# stm32-usb-ble-devkit.net
KiCad netlist of a schematic drawn in EAGLE
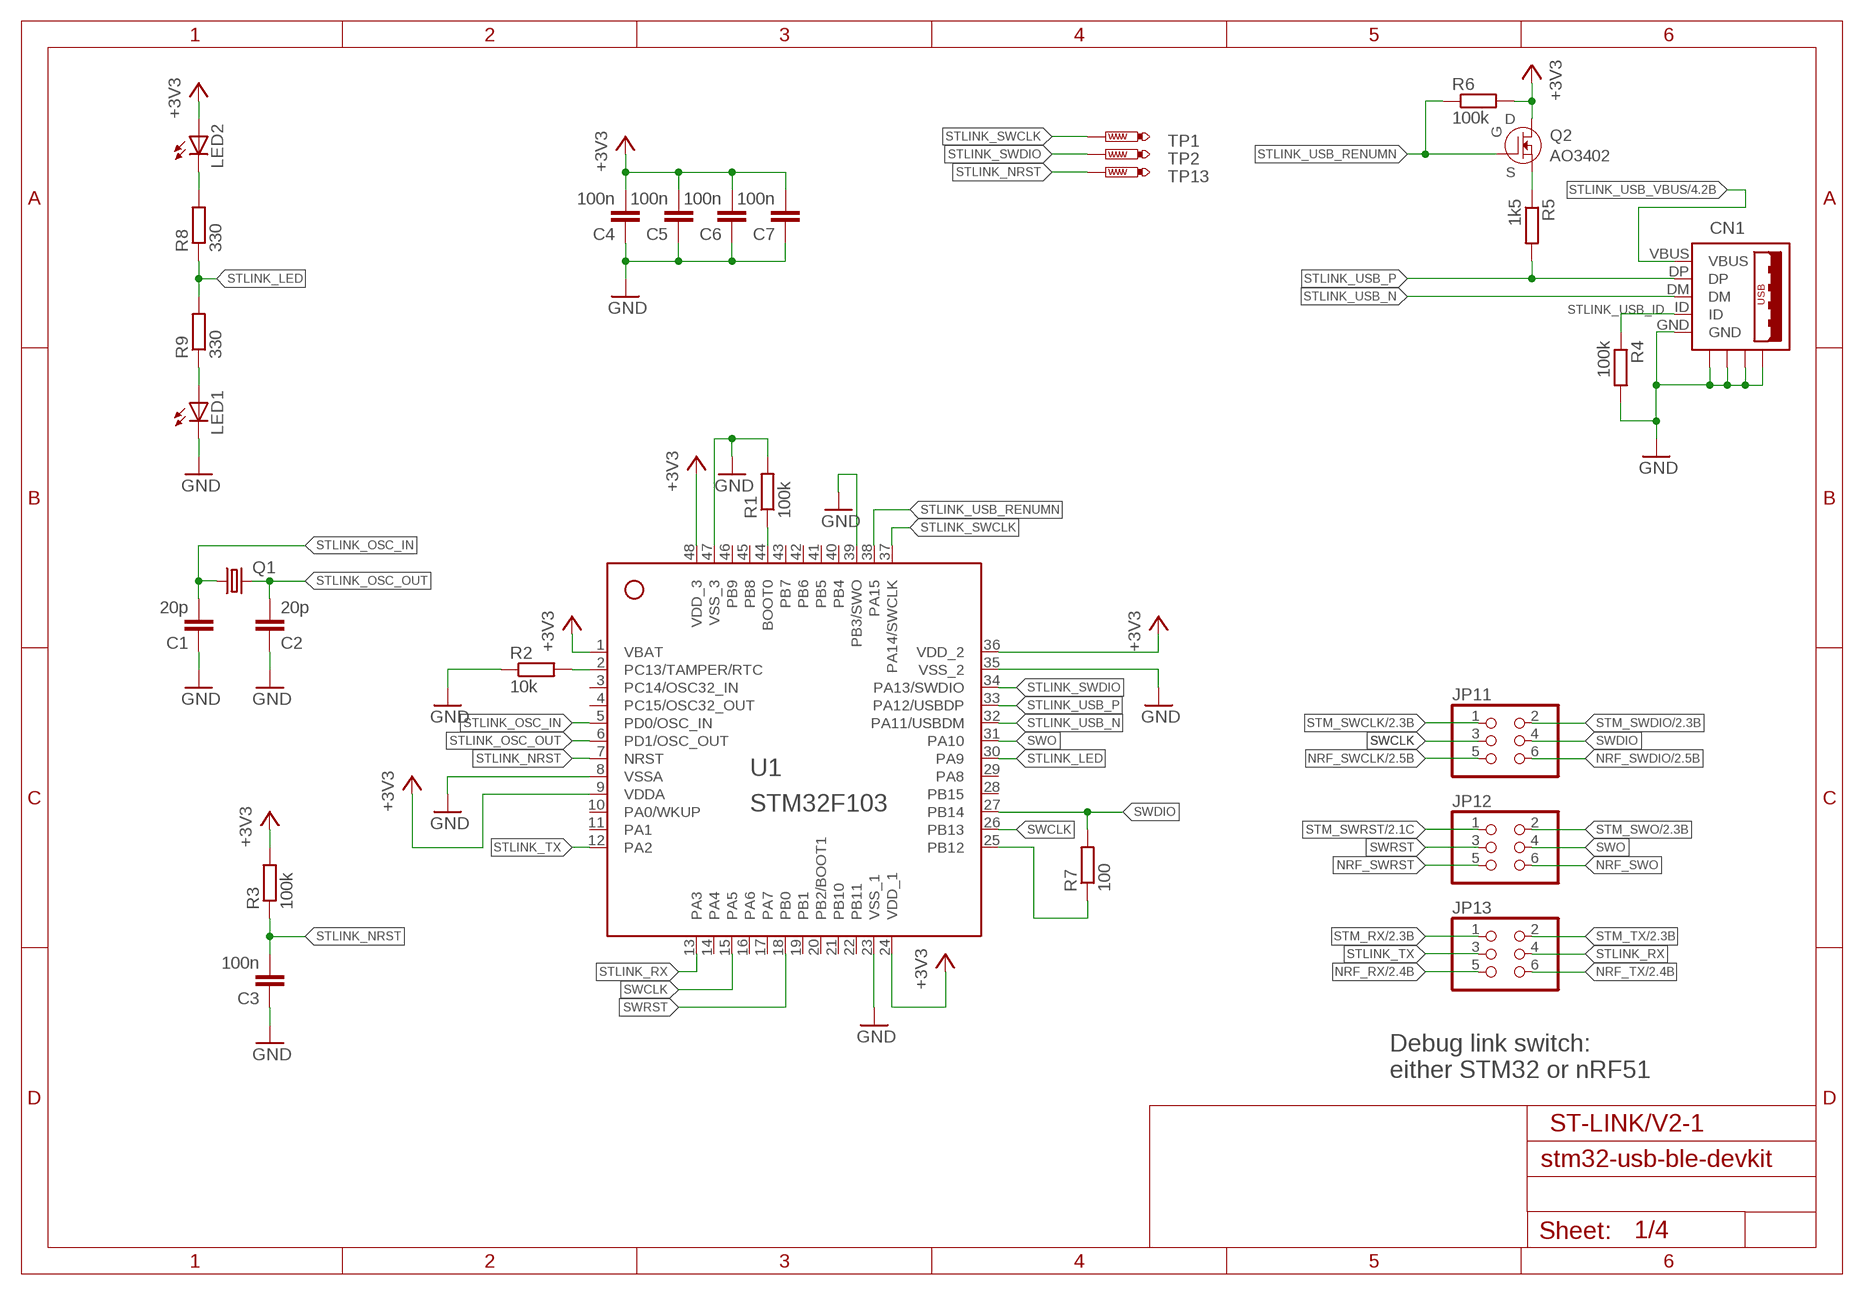
[diagram p0: schematic, sheet 1]
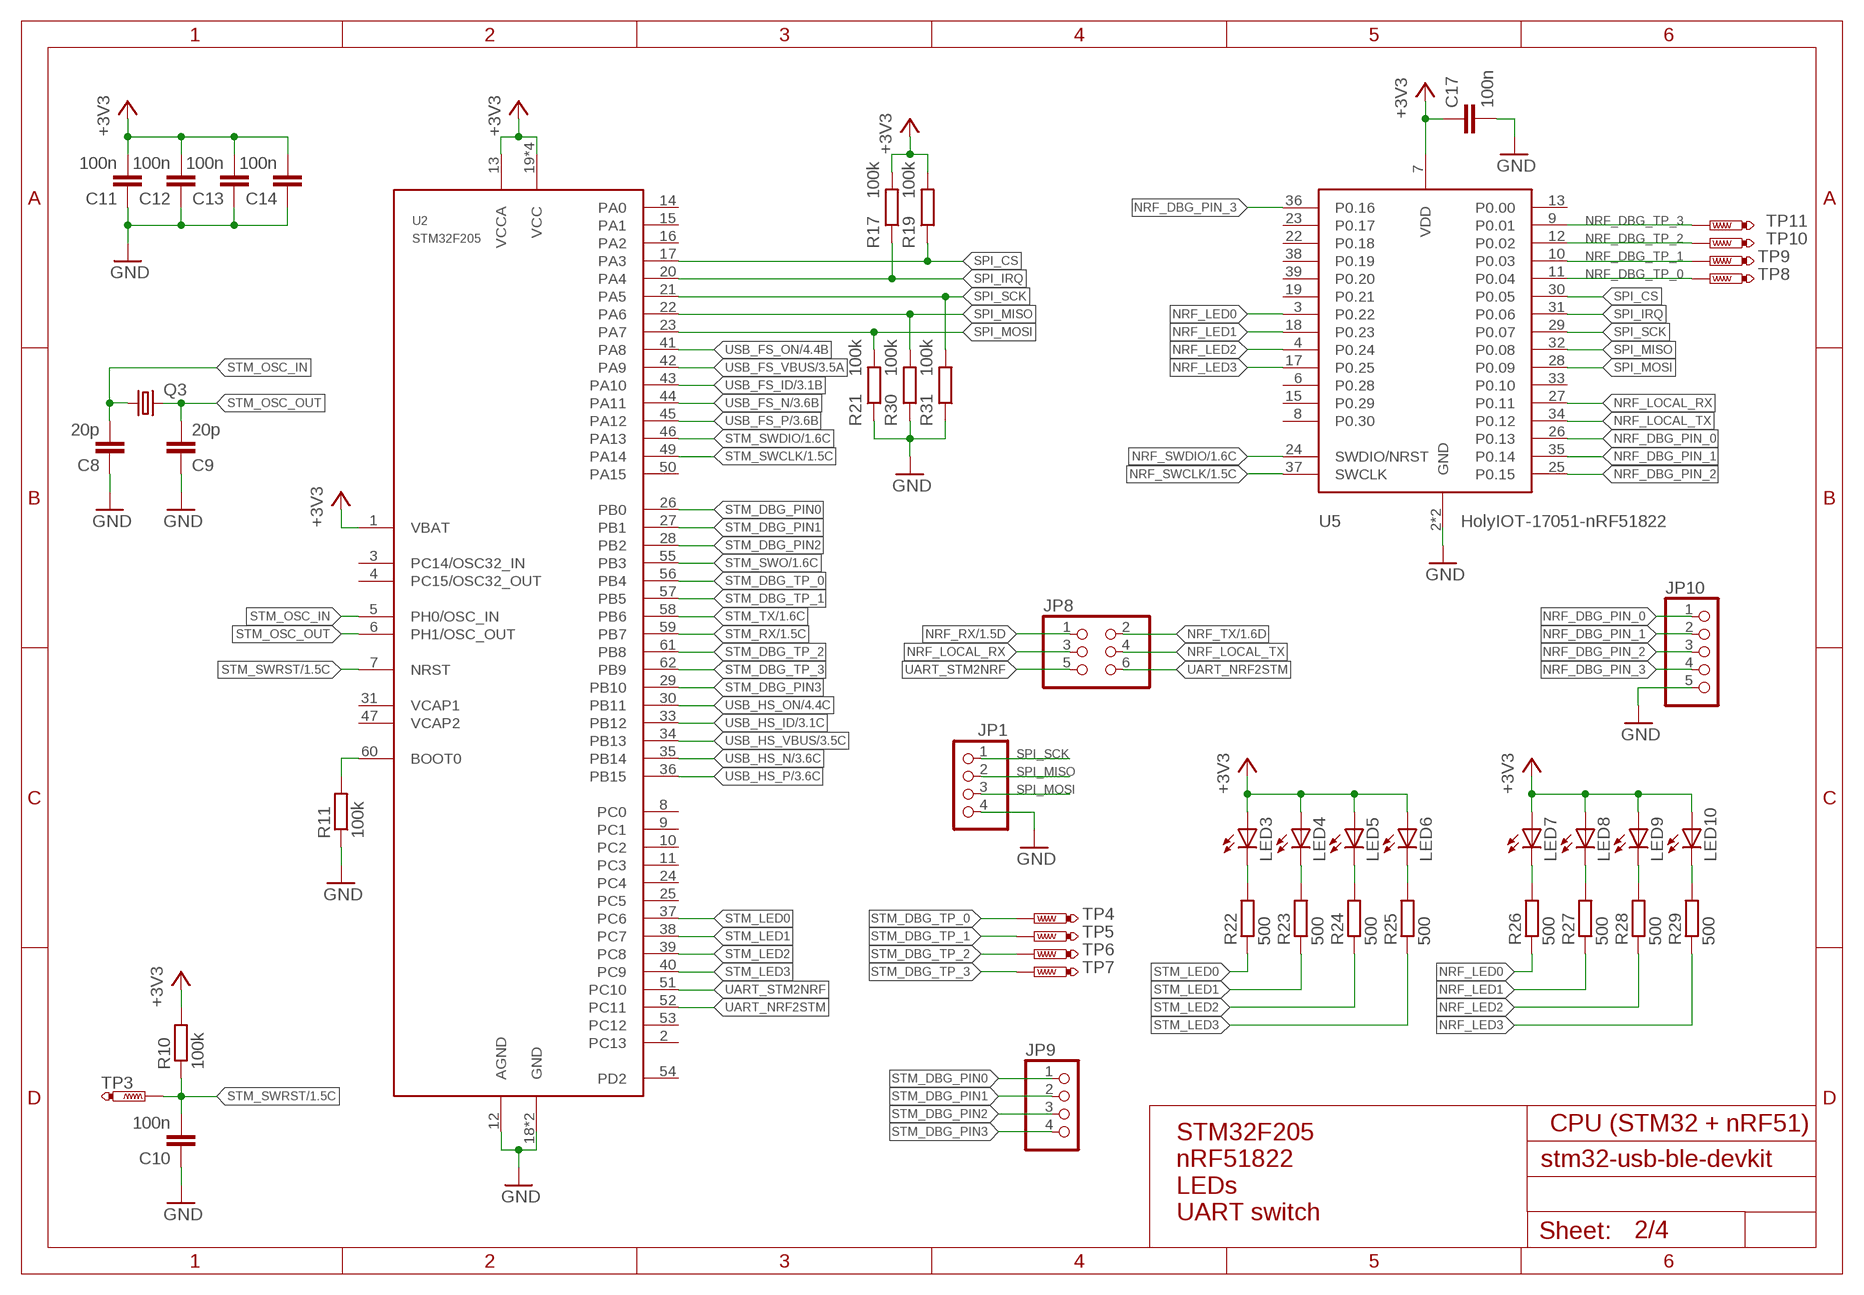
[diagram p1: schematic, sheet 2]
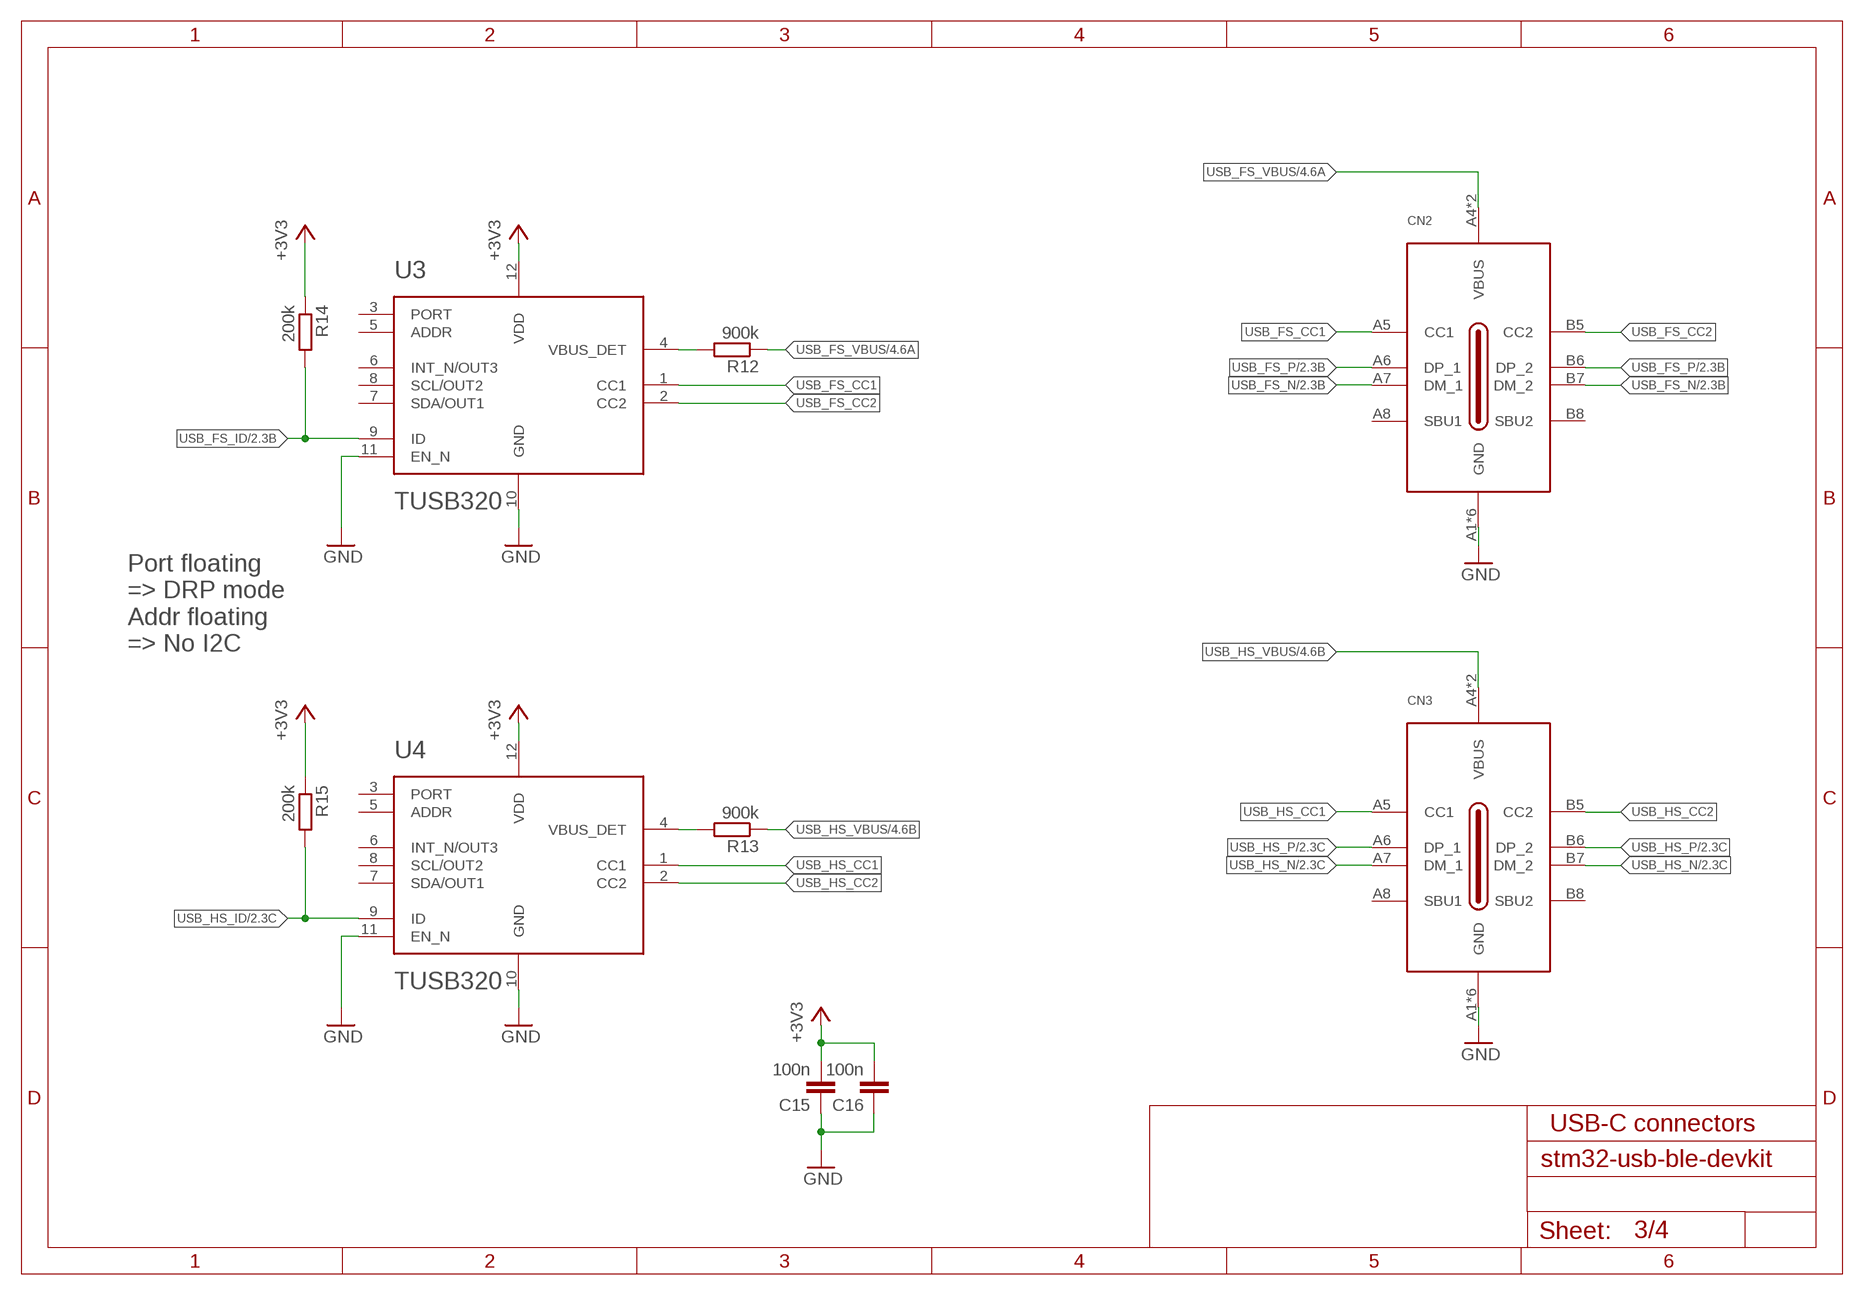
[diagram p2: schematic, sheet 3]
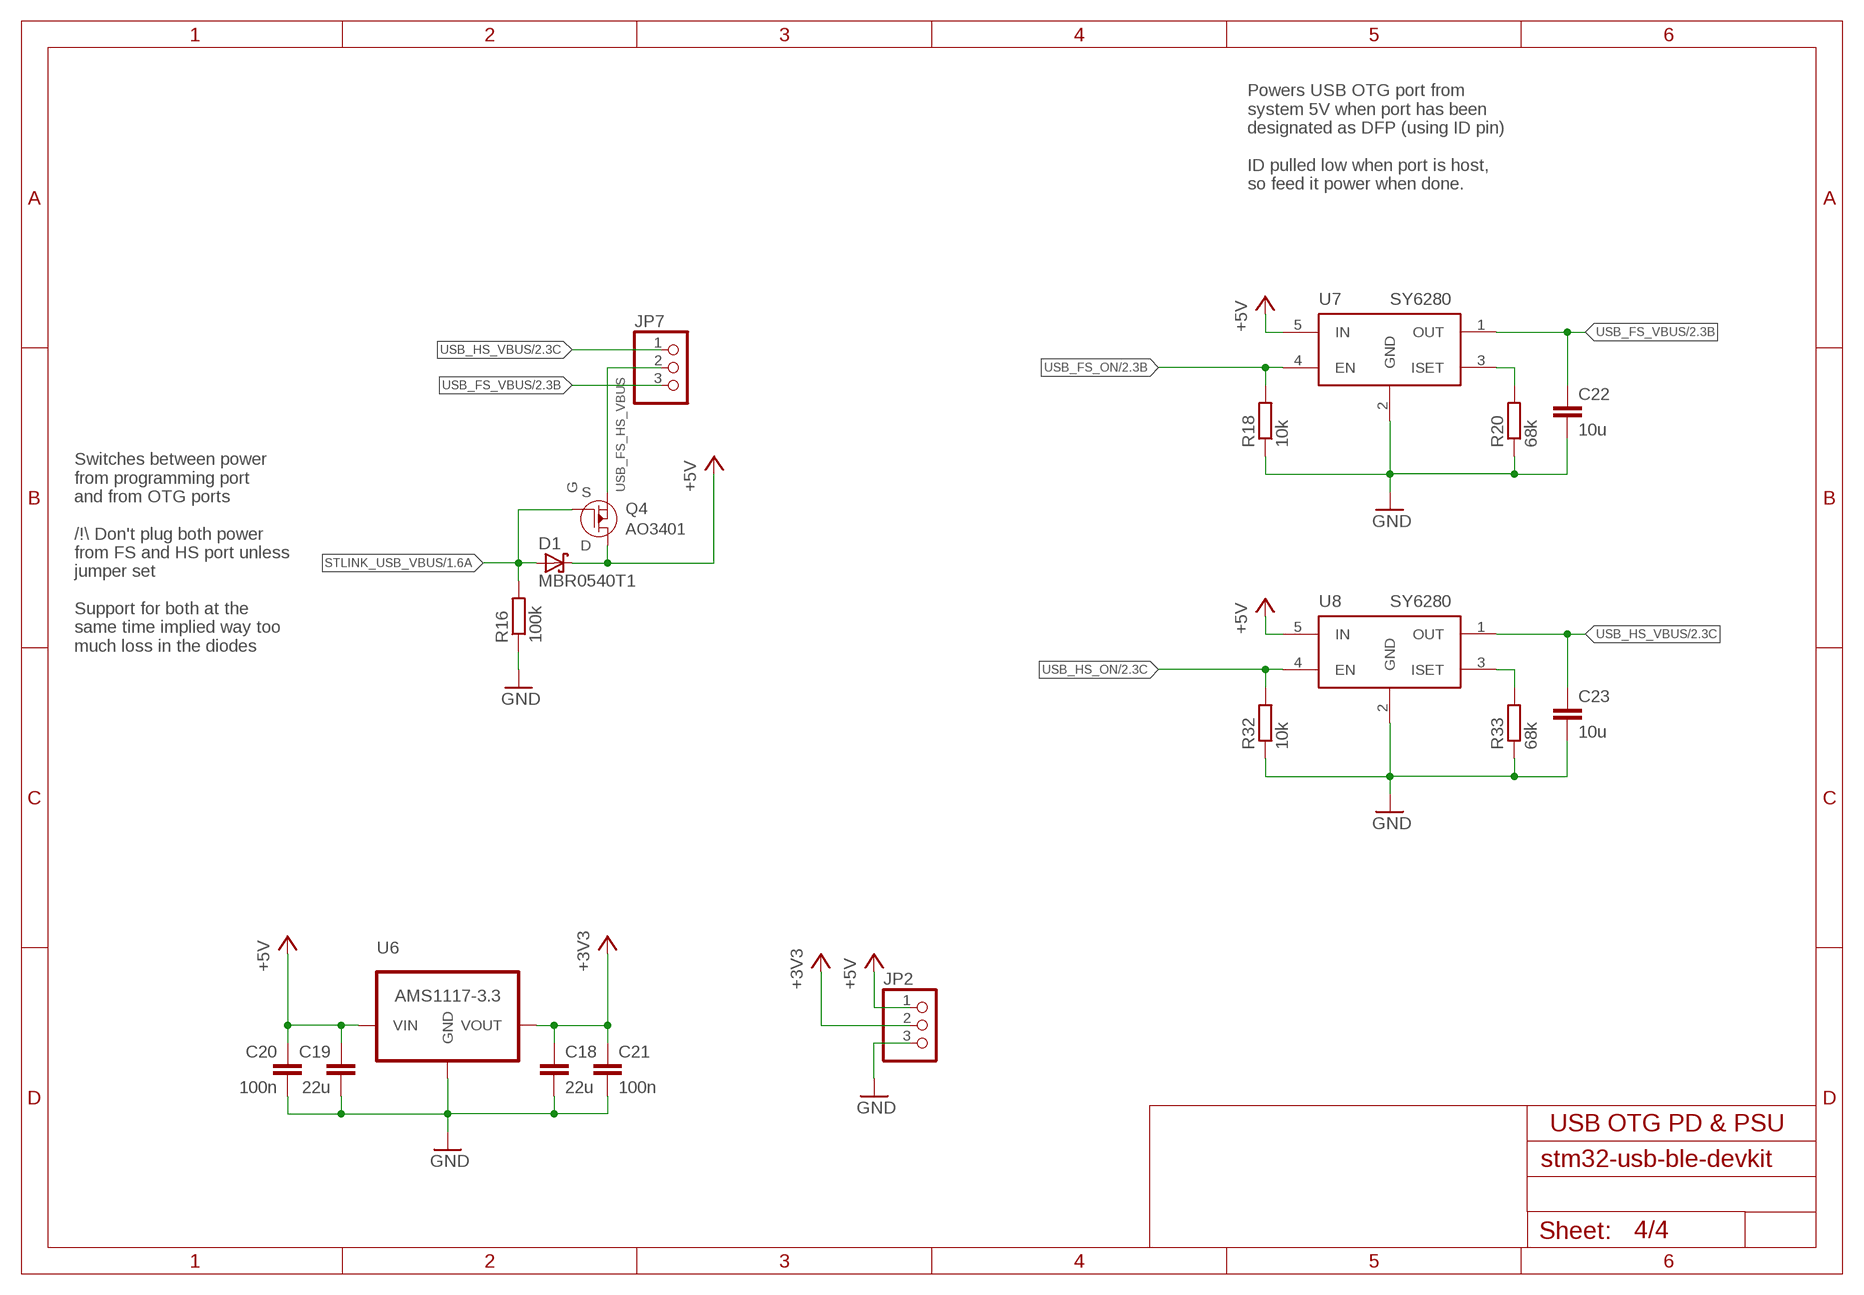
[diagram p3: schematic, sheet 4]

(export (version "E")
  (design (tool "Eeschema 10.0.6"))
  (components
    (comp (ref "C8")
      (value "20p")
      (footprint "eagle-import:0603")
      (libsource (lib "eagle-import") (part "C0603"))
    )
    (comp (ref "C9")
      (value "20p")
      (footprint "eagle-import:0603")
      (libsource (lib "eagle-import") (part "C0603"))
    )
    (comp (ref "C10")
      (value "100n")
      (footprint "eagle-import:0603")
      (libsource (lib "eagle-import") (part "C0603"))
    )
    (comp (ref "C11")
      (value "100n")
      (footprint "eagle-import:0603")
      (libsource (lib "eagle-import") (part "C0603"))
    )
    (comp (ref "C12")
      (value "100n")
      (footprint "eagle-import:0603")
      (libsource (lib "eagle-import") (part "C0603"))
    )
    (comp (ref "C13")
      (value "100n")
      (footprint "eagle-import:0603")
      (libsource (lib "eagle-import") (part "C0603"))
    )
    (comp (ref "C14")
      (value "100n")
      (footprint "eagle-import:0603")
      (libsource (lib "eagle-import") (part "C0603"))
    )
    (comp (ref "C17")
      (value "100n")
      (footprint "eagle-import:0603")
      (libsource (lib "eagle-import") (part "C0603"))
    )
    (comp (ref "JP1")
      (value "PINHD-1X4")
      (footprint "eagle-import:1X04")
      (libsource (lib "eagle-import") (part "PINHD-1X4"))
    )
    (comp (ref "JP8")
      (value "PINHD-2X3")
      (footprint "eagle-import:2X03")
      (libsource (lib "eagle-import") (part "PINHD-2X3"))
    )
    (comp (ref "JP9")
      (value "PINHD-1X4")
      (footprint "eagle-import:1X04")
      (libsource (lib "eagle-import") (part "PINHD-1X4"))
    )
    (comp (ref "JP10")
      (value "PINHD-1X5")
      (footprint "eagle-import:1X05")
      (libsource (lib "eagle-import") (part "PINHD-1X5"))
    )
    (comp (ref "LED3")
      (value "LEDCHIP-LED0603")
      (footprint "eagle-import:CHIP-LED0603")
      (libsource (lib "eagle-import") (part "LEDCHIP-LED0603"))
    )
    (comp (ref "LED4")
      (value "LEDCHIP-LED0603")
      (footprint "eagle-import:CHIP-LED0603")
      (libsource (lib "eagle-import") (part "LEDCHIP-LED0603"))
    )
    (comp (ref "LED5")
      (value "LEDCHIP-LED0603")
      (footprint "eagle-import:CHIP-LED0603")
      (libsource (lib "eagle-import") (part "LEDCHIP-LED0603"))
    )
    (comp (ref "LED6")
      (value "LEDCHIP-LED0603")
      (footprint "eagle-import:CHIP-LED0603")
      (libsource (lib "eagle-import") (part "LEDCHIP-LED0603"))
    )
    (comp (ref "LED7")
      (value "LEDCHIP-LED0603")
      (footprint "eagle-import:CHIP-LED0603")
      (libsource (lib "eagle-import") (part "LEDCHIP-LED0603"))
    )
    (comp (ref "LED8")
      (value "LEDCHIP-LED0603")
      (footprint "eagle-import:CHIP-LED0603")
      (libsource (lib "eagle-import") (part "LEDCHIP-LED0603"))
    )
    (comp (ref "LED9")
      (value "LEDCHIP-LED0603")
      (footprint "eagle-import:CHIP-LED0603")
      (libsource (lib "eagle-import") (part "LEDCHIP-LED0603"))
    )
    (comp (ref "LED10")
      (value "LEDCHIP-LED0603")
      (footprint "eagle-import:CHIP-LED0603")
      (libsource (lib "eagle-import") (part "LEDCHIP-LED0603"))
    )
    (comp (ref "Q3")
      (value "CRYSTALHC49S")
      (footprint "eagle-import:HC49_S")
      (libsource (lib "eagle-import") (part "CRYSTALHC49S"))
    )
    (comp (ref "R10")
      (value "100k")
      (footprint "eagle-import:R0603")
      (libsource (lib "eagle-import") (part "RR0603"))
    )
    (comp (ref "R11")
      (value "100k")
      (footprint "eagle-import:R0603")
      (libsource (lib "eagle-import") (part "RR0603"))
    )
    (comp (ref "R17")
      (value "100k")
      (footprint "eagle-import:R0603")
      (libsource (lib "eagle-import") (part "RR0603"))
    )
    (comp (ref "R19")
      (value "100k")
      (footprint "eagle-import:R0603")
      (libsource (lib "eagle-import") (part "RR0603"))
    )
    (comp (ref "R21")
      (value "100k")
      (footprint "eagle-import:R0603")
      (libsource (lib "eagle-import") (part "RR0603"))
    )
    (comp (ref "R22")
      (value "500")
      (footprint "eagle-import:R0603")
      (libsource (lib "eagle-import") (part "RR0603"))
    )
    (comp (ref "R23")
      (value "500")
      (footprint "eagle-import:R0603")
      (libsource (lib "eagle-import") (part "RR0603"))
    )
    (comp (ref "R24")
      (value "500")
      (footprint "eagle-import:R0603")
      (libsource (lib "eagle-import") (part "RR0603"))
    )
    (comp (ref "R25")
      (value "500")
      (footprint "eagle-import:R0603")
      (libsource (lib "eagle-import") (part "RR0603"))
    )
    (comp (ref "R26")
      (value "500")
      (footprint "eagle-import:R0603")
      (libsource (lib "eagle-import") (part "RR0603"))
    )
    (comp (ref "R27")
      (value "500")
      (footprint "eagle-import:R0603")
      (libsource (lib "eagle-import") (part "RR0603"))
    )
    (comp (ref "R28")
      (value "500")
      (footprint "eagle-import:R0603")
      (libsource (lib "eagle-import") (part "RR0603"))
    )
    (comp (ref "R29")
      (value "500")
      (footprint "eagle-import:R0603")
      (libsource (lib "eagle-import") (part "RR0603"))
    )
    (comp (ref "R30")
      (value "100k")
      (footprint "eagle-import:R0603")
      (libsource (lib "eagle-import") (part "RR0603"))
    )
    (comp (ref "R31")
      (value "100k")
      (footprint "eagle-import:R0603")
      (libsource (lib "eagle-import") (part "RR0603"))
    )
    (comp (ref "TP3")
      (value "PTR1B1,27")
      (footprint "eagle-import:B1,27")
      (libsource (lib "eagle-import") (part "PTR1B1,27"))
    )
    (comp (ref "TP4")
      (value "PTR1B1,27")
      (footprint "eagle-import:B1,27")
      (libsource (lib "eagle-import") (part "PTR1B1,27"))
    )
    (comp (ref "TP5")
      (value "PTR1B1,27")
      (footprint "eagle-import:B1,27")
      (libsource (lib "eagle-import") (part "PTR1B1,27"))
    )
    (comp (ref "TP6")
      (value "PTR1B1,27")
      (footprint "eagle-import:B1,27")
      (libsource (lib "eagle-import") (part "PTR1B1,27"))
    )
    (comp (ref "TP7")
      (value "PTR1B1,27")
      (footprint "eagle-import:B1,27")
      (libsource (lib "eagle-import") (part "PTR1B1,27"))
    )
    (comp (ref "TP8")
      (value "PTR1B1,27")
      (footprint "eagle-import:B1,27")
      (libsource (lib "eagle-import") (part "PTR1B1,27"))
    )
    (comp (ref "TP9")
      (value "PTR1B1,27")
      (footprint "eagle-import:B1,27")
      (libsource (lib "eagle-import") (part "PTR1B1,27"))
    )
    (comp (ref "TP10")
      (value "PTR1B1,27")
      (footprint "eagle-import:B1,27")
      (libsource (lib "eagle-import") (part "PTR1B1,27"))
    )
    (comp (ref "TP11")
      (value "PTR1B1,27")
      (footprint "eagle-import:B1,27")
      (libsource (lib "eagle-import") (part "PTR1B1,27"))
    )
    (comp (ref "U2")
      (value "STM32F205-64")
      (footprint "eagle-import:LQFP-64")
      (libsource (lib "eagle-import") (part "STM32F205-64"))
    )
    (comp (ref "U5")
      (value "HOLYIOT-17051-NRF51822")
      (footprint "eagle-import:HOLYIOT-17051-NRF51822")
      (libsource (lib "eagle-import") (part "HOLYIOT-17051-NRF51822"))
    )
    (comp (ref "C18")
      (value "22u")
      (footprint "eagle-import:0603")
      (libsource (lib "eagle-import") (part "C0603"))
    )
    (comp (ref "C19")
      (value "22u")
      (footprint "eagle-import:0603")
      (libsource (lib "eagle-import") (part "C0603"))
    )
    (comp (ref "C20")
      (value "100n")
      (footprint "eagle-import:0603")
      (libsource (lib "eagle-import") (part "C0603"))
    )
    (comp (ref "C21")
      (value "100n")
      (footprint "eagle-import:0603")
      (libsource (lib "eagle-import") (part "C0603"))
    )
    (comp (ref "C22")
      (value "10u")
      (footprint "eagle-import:0603")
      (libsource (lib "eagle-import") (part "C0603"))
    )
    (comp (ref "C23")
      (value "10u")
      (footprint "eagle-import:0603")
      (libsource (lib "eagle-import") (part "C0603"))
    )
    (comp (ref "D1")
      (value "MBR0540T1")
      (footprint "eagle-import:SOD123")
      (libsource (lib "eagle-import") (part "MBR0540T1"))
    )
    (comp (ref "JP2")
      (value "PINHD-1X3")
      (footprint "eagle-import:1X03")
      (libsource (lib "eagle-import") (part "PINHD-1X3"))
    )
    (comp (ref "JP7")
      (value "PINHD-1X3")
      (footprint "eagle-import:1X03")
      (libsource (lib "eagle-import") (part "PINHD-1X3"))
    )
    (comp (ref "Q4")
      (value "AO3401")
      (footprint "eagle-import:SOT23-3")
      (libsource (lib "eagle-import") (part "AO3401"))
    )
    (comp (ref "R16")
      (value "100k")
      (footprint "eagle-import:R0603")
      (libsource (lib "eagle-import") (part "RR0603"))
    )
    (comp (ref "R18")
      (value "10k")
      (footprint "eagle-import:R0603")
      (libsource (lib "eagle-import") (part "RR0603"))
    )
    (comp (ref "R20")
      (value "68k")
      (footprint "eagle-import:R0603")
      (libsource (lib "eagle-import") (part "RR0603"))
    )
    (comp (ref "R32")
      (value "10k")
      (footprint "eagle-import:R0603")
      (libsource (lib "eagle-import") (part "RR0603"))
    )
    (comp (ref "R33")
      (value "68k")
      (footprint "eagle-import:R0603")
      (libsource (lib "eagle-import") (part "RR0603"))
    )
    (comp (ref "U6")
      (value "AMS1117-3.3")
      (footprint "eagle-import:SOT223")
      (libsource (lib "eagle-import") (part "LDOAMS1117"))
    )
    (comp (ref "U7")
      (value "SY6280")
      (footprint "eagle-import:SOT23-5")
      (libsource (lib "eagle-import") (part "SY6280"))
    )
    (comp (ref "U8")
      (value "SY6280")
      (footprint "eagle-import:SOT23-5")
      (libsource (lib "eagle-import") (part "SY6280"))
    )
    (comp (ref "C15")
      (value "100n")
      (footprint "eagle-import:0603")
      (libsource (lib "eagle-import") (part "C0603"))
    )
    (comp (ref "C16")
      (value "100n")
      (footprint "eagle-import:0603")
      (libsource (lib "eagle-import") (part "C0603"))
    )
    (comp (ref "CN2")
      (value "USB-C-2.0-FEMALE")
      (footprint "eagle-import:USB-C-FEMALE")
      (libsource (lib "eagle-import") (part "USB-C-2.0-FEMALE"))
    )
    (comp (ref "CN3")
      (value "USB-C-2.0-FEMALE")
      (footprint "eagle-import:USB-C-FEMALE")
      (libsource (lib "eagle-import") (part "USB-C-2.0-FEMALE"))
    )
    (comp (ref "R12")
      (value "900k")
      (footprint "eagle-import:R0603")
      (libsource (lib "eagle-import") (part "RR0603"))
    )
    (comp (ref "R13")
      (value "900k")
      (footprint "eagle-import:R0603")
      (libsource (lib "eagle-import") (part "RR0603"))
    )
    (comp (ref "R14")
      (value "200k")
      (footprint "eagle-import:R0603")
      (libsource (lib "eagle-import") (part "RR0603"))
    )
    (comp (ref "R15")
      (value "200k")
      (footprint "eagle-import:R0603")
      (libsource (lib "eagle-import") (part "RR0603"))
    )
    (comp (ref "U3")
      (value "TUSB320")
      (footprint "eagle-import:X2QFN-0.4")
      (libsource (lib "eagle-import") (part "TUSB320"))
    )
    (comp (ref "U4")
      (value "TUSB320")
      (footprint "eagle-import:X2QFN-0.4")
      (libsource (lib "eagle-import") (part "TUSB320"))
    )
    (comp (ref "C1")
      (value "20p")
      (footprint "eagle-import:0603")
      (libsource (lib "eagle-import") (part "C0603"))
    )
    (comp (ref "C2")
      (value "20p")
      (footprint "eagle-import:0603")
      (libsource (lib "eagle-import") (part "C0603"))
    )
    (comp (ref "C3")
      (value "100n")
      (footprint "eagle-import:0603")
      (libsource (lib "eagle-import") (part "C0603"))
    )
    (comp (ref "C4")
      (value "100n")
      (footprint "eagle-import:0603")
      (libsource (lib "eagle-import") (part "C0603"))
    )
    (comp (ref "C5")
      (value "100n")
      (footprint "eagle-import:0603")
      (libsource (lib "eagle-import") (part "C0603"))
    )
    (comp (ref "C6")
      (value "100n")
      (footprint "eagle-import:0603")
      (libsource (lib "eagle-import") (part "C0603"))
    )
    (comp (ref "C7")
      (value "100n")
      (footprint "eagle-import:0603")
      (libsource (lib "eagle-import") (part "C0603"))
    )
    (comp (ref "CN1")
      (value "USB-MICROB-2TABS")
      (footprint "eagle-import:USB-MICROB-2")
      (libsource (lib "eagle-import") (part "USB-MICROB-2TABS"))
    )
    (comp (ref "JP11")
      (value "PINHD-2X3")
      (footprint "eagle-import:2X03")
      (libsource (lib "eagle-import") (part "PINHD-2X3"))
    )
    (comp (ref "JP12")
      (value "PINHD-2X3")
      (footprint "eagle-import:2X03")
      (libsource (lib "eagle-import") (part "PINHD-2X3"))
    )
    (comp (ref "JP13")
      (value "PINHD-2X3")
      (footprint "eagle-import:2X03")
      (libsource (lib "eagle-import") (part "PINHD-2X3"))
    )
    (comp (ref "LED1")
      (value "LEDCHIP-LED0603")
      (footprint "eagle-import:CHIP-LED0603")
      (libsource (lib "eagle-import") (part "LEDCHIP-LED0603"))
    )
    (comp (ref "LED2")
      (value "LEDCHIP-LED0603")
      (footprint "eagle-import:CHIP-LED0603")
      (libsource (lib "eagle-import") (part "LEDCHIP-LED0603"))
    )
    (comp (ref "Q1")
      (value "CRYSTALHC49S")
      (footprint "eagle-import:HC49_S")
      (libsource (lib "eagle-import") (part "CRYSTALHC49S"))
    )
    (comp (ref "Q2")
      (value "AO3402")
      (footprint "eagle-import:SOT23-3")
      (libsource (lib "eagle-import") (part "AO3402"))
    )
    (comp (ref "R1")
      (value "100k")
      (footprint "eagle-import:R0603")
      (libsource (lib "eagle-import") (part "RR0603"))
    )
    (comp (ref "R2")
      (value "10k")
      (footprint "eagle-import:R0603")
      (libsource (lib "eagle-import") (part "RR0603"))
    )
    (comp (ref "R3")
      (value "100k")
      (footprint "eagle-import:R0603")
      (libsource (lib "eagle-import") (part "RR0603"))
    )
    (comp (ref "R4")
      (value "100k")
      (footprint "eagle-import:R0603")
      (libsource (lib "eagle-import") (part "RR0603"))
    )
    (comp (ref "R5")
      (value "1k5")
      (footprint "eagle-import:R0603")
      (libsource (lib "eagle-import") (part "RR0603"))
    )
    (comp (ref "R6")
      (value "100k")
      (footprint "eagle-import:R0603")
      (libsource (lib "eagle-import") (part "RR0603"))
    )
    (comp (ref "R7")
      (value "100")
      (footprint "eagle-import:R0603")
      (libsource (lib "eagle-import") (part "RR0603"))
    )
    (comp (ref "R8")
      (value "330")
      (footprint "eagle-import:R0603")
      (libsource (lib "eagle-import") (part "RR0603"))
    )
    (comp (ref "R9")
      (value "330")
      (footprint "eagle-import:R0603")
      (libsource (lib "eagle-import") (part "RR0603"))
    )
    (comp (ref "TP1")
      (value "PTR1B1,27")
      (footprint "eagle-import:B1,27")
      (libsource (lib "eagle-import") (part "PTR1B1,27"))
    )
    (comp (ref "TP2")
      (value "PTR1B1,27")
      (footprint "eagle-import:B1,27")
      (libsource (lib "eagle-import") (part "PTR1B1,27"))
    )
    (comp (ref "TP13")
      (value "PTR1B1,27")
      (footprint "eagle-import:B1,27")
      (libsource (lib "eagle-import") (part "PTR1B1,27"))
    )
    (comp (ref "U1")
      (value "STM32F103-48LQFP")
      (footprint "eagle-import:LQFP-48")
      (libsource (lib "eagle-import") (part "STM32F103-48LQFP"))
    )
  )
  (nets
    (net (code "1") (name "+3V3") (class "Default")
      (node (ref "C11") (pin "2") (pinfunction "2_2") (pintype "passive"))
      (node (ref "C12") (pin "2") (pinfunction "2_2") (pintype "passive"))
      (node (ref "C13") (pin "2") (pinfunction "2_2") (pintype "passive"))
      (node (ref "C14") (pin "2") (pinfunction "2_2") (pintype "passive"))
      (node (ref "C15") (pin "2") (pinfunction "2_2") (pintype "passive"))
      (node (ref "C16") (pin "2") (pinfunction "2_2") (pintype "passive"))
      (node (ref "C17") (pin "1") (pinfunction "1_1") (pintype "passive"))
      (node (ref "C18") (pin "1") (pinfunction "1_1") (pintype "passive"))
      (node (ref "C21") (pin "1") (pinfunction "1_1") (pintype "passive"))
      (node (ref "C4") (pin "2") (pinfunction "2_2") (pintype "passive"))
      (node (ref "C5") (pin "2") (pinfunction "2_2") (pintype "passive"))
      (node (ref "C6") (pin "2") (pinfunction "2_2") (pintype "passive"))
      (node (ref "C7") (pin "2") (pinfunction "2_2") (pintype "passive"))
      (node (ref "JP2") (pin "2") (pinfunction "2_2") (pintype "passive"))
      (node (ref "LED10") (pin "A") (pinfunction "A_A") (pintype "passive"))
      (node (ref "LED2") (pin "A") (pinfunction "A_A") (pintype "passive"))
      (node (ref "LED3") (pin "A") (pinfunction "A_A") (pintype "passive"))
      (node (ref "LED4") (pin "A") (pinfunction "A_A") (pintype "passive"))
      (node (ref "LED5") (pin "A") (pinfunction "A_A") (pintype "passive"))
      (node (ref "LED6") (pin "A") (pinfunction "A_A") (pintype "passive"))
      (node (ref "LED7") (pin "A") (pinfunction "A_A") (pintype "passive"))
      (node (ref "LED8") (pin "A") (pinfunction "A_A") (pintype "passive"))
      (node (ref "LED9") (pin "A") (pinfunction "A_A") (pintype "passive"))
      (node (ref "Q2") (pin "3") (pinfunction "D_3") (pintype "bidirectional"))
      (node (ref "R10") (pin "2") (pinfunction "2_2") (pintype "passive"))
      (node (ref "R14") (pin "1") (pinfunction "1_1") (pintype "passive"))
      (node (ref "R15") (pin "1") (pinfunction "1_1") (pintype "passive"))
      (node (ref "R17") (pin "2") (pinfunction "2_2") (pintype "passive"))
      (node (ref "R19") (pin "2") (pinfunction "2_2") (pintype "passive"))
      (node (ref "R3") (pin "2") (pinfunction "2_2") (pintype "passive"))
      (node (ref "R6") (pin "2") (pinfunction "2_2") (pintype "passive"))
      (node (ref "U1") (pin "1") (pinfunction "VBAT_1") (pintype "bidirectional"))
      (node (ref "U1") (pin "24") (pinfunction "VDD_1_24") (pintype "bidirectional"))
      (node (ref "U1") (pin "36") (pinfunction "VDD_2_36") (pintype "bidirectional"))
      (node (ref "U1") (pin "48") (pinfunction "VDD_3_48") (pintype "bidirectional"))
      (node (ref "U1") (pin "9") (pinfunction "VDDA_9") (pintype "bidirectional"))
      (node (ref "U2") (pin "1") (pinfunction "VBAT_1") (pintype "bidirectional"))
      (node (ref "U2") (pin "13") (pinfunction "VCCA_13") (pintype "power_in"))
      (node (ref "U2") (pin "19") (pinfunction "VCC_19") (pintype "power_in"))
      (node (ref "U2") (pin "32") (pinfunction "VCC_32") (pintype "power_in"))
      (node (ref "U2") (pin "48") (pinfunction "VCC_48") (pintype "power_in"))
      (node (ref "U2") (pin "64") (pinfunction "VCC_64") (pintype "power_in"))
      (node (ref "U3") (pin "12") (pinfunction "VDD_12") (pintype "bidirectional"))
      (node (ref "U4") (pin "12") (pinfunction "VDD_12") (pintype "bidirectional"))
      (node (ref "U5") (pin "7") (pinfunction "VDD_7") (pintype "power_in"))
      (node (ref "U6") (pin "2") (pinfunction "VOUT_2") (pintype "passive"))
    )
    (net (code "2") (name "+5V") (class "Default")
      (node (ref "C19") (pin "1") (pinfunction "1_1") (pintype "passive"))
      (node (ref "C20") (pin "1") (pinfunction "1_1") (pintype "passive"))
      (node (ref "D1") (pin "C") (pinfunction "C_C") (pintype "passive"))
      (node (ref "JP2") (pin "1") (pinfunction "1_1") (pintype "passive"))
      (node (ref "Q4") (pin "3") (pinfunction "D_3") (pintype "bidirectional"))
      (node (ref "U6") (pin "3") (pinfunction "VIN_3") (pintype "passive"))
      (node (ref "U7") (pin "5") (pinfunction "IN_5") (pintype "bidirectional"))
      (node (ref "U8") (pin "5") (pinfunction "IN_5") (pintype "bidirectional"))
    )
    (net (code "3") (name "GND") (class "Default")
      (node (ref "C1") (pin "1") (pinfunction "1_1") (pintype "passive"))
      (node (ref "C10") (pin "1") (pinfunction "1_1") (pintype "passive"))
      (node (ref "C11") (pin "1") (pinfunction "1_1") (pintype "passive"))
      (node (ref "C12") (pin "1") (pinfunction "1_1") (pintype "passive"))
      (node (ref "C13") (pin "1") (pinfunction "1_1") (pintype "passive"))
      (node (ref "C14") (pin "1") (pinfunction "1_1") (pintype "passive"))
      (node (ref "C15") (pin "1") (pinfunction "1_1") (pintype "passive"))
      (node (ref "C16") (pin "1") (pinfunction "1_1") (pintype "passive"))
      (node (ref "C17") (pin "2") (pinfunction "2_2") (pintype "passive"))
      (node (ref "C18") (pin "2") (pinfunction "2_2") (pintype "passive"))
      (node (ref "C19") (pin "2") (pinfunction "2_2") (pintype "passive"))
      (node (ref "C2") (pin "1") (pinfunction "1_1") (pintype "passive"))
      (node (ref "C20") (pin "2") (pinfunction "2_2") (pintype "passive"))
      (node (ref "C21") (pin "2") (pinfunction "2_2") (pintype "passive"))
      (node (ref "C22") (pin "2") (pinfunction "2_2") (pintype "passive"))
      (node (ref "C23") (pin "2") (pinfunction "2_2") (pintype "passive"))
      (node (ref "C3") (pin "1") (pinfunction "1_1") (pintype "passive"))
      (node (ref "C4") (pin "1") (pinfunction "1_1") (pintype "passive"))
      (node (ref "C5") (pin "1") (pinfunction "1_1") (pintype "passive"))
      (node (ref "C6") (pin "1") (pinfunction "1_1") (pintype "passive"))
      (node (ref "C7") (pin "1") (pinfunction "1_1") (pintype "passive"))
      (node (ref "C8") (pin "1") (pinfunction "1_1") (pintype "passive"))
      (node (ref "C9") (pin "1") (pinfunction "1_1") (pintype "passive"))
      (node (ref "CN1") (pin "GND") (pinfunction "GND_GND") (pintype "passive"))
      (node (ref "CN1") (pin "GND@1") (pinfunction "GND_GND@1") (pintype "power_in"))
      (node (ref "CN1") (pin "GND@2") (pinfunction "GND_GND@2") (pintype "power_in"))
      (node (ref "CN1") (pin "GND@3") (pinfunction "GND_GND@3") (pintype "power_in"))
      (node (ref "CN1") (pin "GND@4") (pinfunction "GND_GND@4") (pintype "power_in"))
      (node (ref "CN2") (pin "A1") (pinfunction "GND_A1") (pintype "bidirectional"))
      (node (ref "CN2") (pin "A12") (pinfunction "GND_A12") (pintype "bidirectional"))
      (node (ref "CN2") (pin "G1") (pinfunction "GND_G1") (pintype "bidirectional"))
      (node (ref "CN2") (pin "G2") (pinfunction "GND_G2") (pintype "bidirectional"))
      (node (ref "CN2") (pin "G3") (pinfunction "GND_G3") (pintype "bidirectional"))
      (node (ref "CN2") (pin "G4") (pinfunction "GND_G4") (pintype "bidirectional"))
      (node (ref "CN3") (pin "A1") (pinfunction "GND_A1") (pintype "bidirectional"))
      (node (ref "CN3") (pin "A12") (pinfunction "GND_A12") (pintype "bidirectional"))
      (node (ref "CN3") (pin "G1") (pinfunction "GND_G1") (pintype "bidirectional"))
      (node (ref "CN3") (pin "G2") (pinfunction "GND_G2") (pintype "bidirectional"))
      (node (ref "CN3") (pin "G3") (pinfunction "GND_G3") (pintype "bidirectional"))
      (node (ref "CN3") (pin "G4") (pinfunction "GND_G4") (pintype "bidirectional"))
      (node (ref "JP1") (pin "4") (pinfunction "4_4") (pintype "passive"))
      (node (ref "JP10") (pin "5") (pinfunction "5_5") (pintype "passive"))
      (node (ref "JP2") (pin "3") (pinfunction "3_3") (pintype "passive"))
      (node (ref "LED1") (pin "C") (pinfunction "C_C") (pintype "passive"))
      (node (ref "R1") (pin "2") (pinfunction "2_2") (pintype "passive"))
      (node (ref "R11") (pin "1") (pinfunction "1_1") (pintype "passive"))
      (node (ref "R16") (pin "1") (pinfunction "1_1") (pintype "passive"))
      (node (ref "R18") (pin "1") (pinfunction "1_1") (pintype "passive"))
      (node (ref "R2") (pin "1") (pinfunction "1_1") (pintype "passive"))
      (node (ref "R20") (pin "1") (pinfunction "1_1") (pintype "passive"))
      (node (ref "R21") (pin "1") (pinfunction "1_1") (pintype "passive"))
      (node (ref "R30") (pin "1") (pinfunction "1_1") (pintype "passive"))
      (node (ref "R31") (pin "1") (pinfunction "1_1") (pintype "passive"))
      (node (ref "R32") (pin "1") (pinfunction "1_1") (pintype "passive"))
      (node (ref "R33") (pin "1") (pinfunction "1_1") (pintype "passive"))
      (node (ref "R4") (pin "2") (pinfunction "2_2") (pintype "passive"))
      (node (ref "U1") (pin "23") (pinfunction "VSS_1_23") (pintype "bidirectional"))
      (node (ref "U1") (pin "35") (pinfunction "VSS_2_35") (pintype "bidirectional"))
      (node (ref "U1") (pin "39") (pinfunction "PB3/SWO_39") (pintype "bidirectional"))
      (node (ref "U1") (pin "47") (pinfunction "VSS_3_47") (pintype "bidirectional"))
      (node (ref "U1") (pin "8") (pinfunction "VSSA_8") (pintype "bidirectional"))
      (node (ref "U2") (pin "12") (pinfunction "AGND_12") (pintype "power_in"))
      (node (ref "U2") (pin "18") (pinfunction "GND_18") (pintype "power_in"))
      (node (ref "U2") (pin "63") (pinfunction "GND_63") (pintype "power_in"))
      (node (ref "U3") (pin "10") (pinfunction "GND_10") (pintype "bidirectional"))
      (node (ref "U3") (pin "11") (pinfunction "EN_N_11") (pintype "bidirectional"))
      (node (ref "U4") (pin "10") (pinfunction "GND_10") (pintype "bidirectional"))
      (node (ref "U4") (pin "11") (pinfunction "EN_N_11") (pintype "bidirectional"))
      (node (ref "U5") (pin "14") (pinfunction "GND_14") (pintype "power_in"))
      (node (ref "U5") (pin "2") (pinfunction "GND_2") (pintype "power_in"))
      (node (ref "U6") (pin "1") (pinfunction "GND_1") (pintype "passive"))
      (node (ref "U7") (pin "2") (pinfunction "GND_2") (pintype "bidirectional"))
      (node (ref "U8") (pin "2") (pinfunction "GND_2") (pintype "bidirectional"))
    )
    (net (code "4") (name "NRF_DBG_PIN_0") (class "Default")
      (node (ref "JP10") (pin "1") (pinfunction "1_1") (pintype "passive"))
      (node (ref "U5") (pin "26") (pinfunction "P0.13_26") (pintype "bidirectional"))
    )
    (net (code "5") (name "NRF_DBG_PIN_1") (class "Default")
      (node (ref "JP10") (pin "2") (pinfunction "2_2") (pintype "passive"))
      (node (ref "U5") (pin "35") (pinfunction "P0.14_35") (pintype "bidirectional"))
    )
    (net (code "6") (name "NRF_DBG_PIN_2") (class "Default")
      (node (ref "JP10") (pin "3") (pinfunction "3_3") (pintype "passive"))
      (node (ref "U5") (pin "25") (pinfunction "P0.15_25") (pintype "bidirectional"))
    )
    (net (code "7") (name "NRF_DBG_PIN_3") (class "Default")
      (node (ref "JP10") (pin "4") (pinfunction "4_4") (pintype "passive"))
      (node (ref "U5") (pin "36") (pinfunction "P0.16_36") (pintype "bidirectional"))
    )
    (net (code "8") (name "NRF_DBG_TP_0") (class "Default")
      (node (ref "TP8") (pin "TP") (pinfunction "TP_TP") (pintype "input"))
      (node (ref "U5") (pin "11") (pinfunction "P0.04_11") (pintype "bidirectional"))
    )
    (net (code "9") (name "NRF_DBG_TP_1") (class "Default")
      (node (ref "TP9") (pin "TP") (pinfunction "TP_TP") (pintype "input"))
      (node (ref "U5") (pin "10") (pinfunction "P0.03_10") (pintype "bidirectional"))
    )
    (net (code "10") (name "NRF_DBG_TP_2") (class "Default")
      (node (ref "TP10") (pin "TP") (pinfunction "TP_TP") (pintype "input"))
      (node (ref "U5") (pin "12") (pinfunction "P0.02_12") (pintype "bidirectional"))
    )
    (net (code "11") (name "NRF_DBG_TP_3") (class "Default")
      (node (ref "TP11") (pin "TP") (pinfunction "TP_TP") (pintype "input"))
      (node (ref "U5") (pin "9") (pinfunction "P0.01_9") (pintype "bidirectional"))
    )
    (net (code "12") (name "NRF_LED0") (class "Default")
      (node (ref "R26") (pin "1") (pinfunction "1_1") (pintype "passive"))
      (node (ref "U5") (pin "3") (pinfunction "P0.22_3") (pintype "bidirectional"))
    )
    (net (code "13") (name "NRF_LED1") (class "Default")
      (node (ref "R27") (pin "1") (pinfunction "1_1") (pintype "passive"))
      (node (ref "U5") (pin "18") (pinfunction "P0.23_18") (pintype "bidirectional"))
    )
    (net (code "14") (name "NRF_LED2") (class "Default")
      (node (ref "R28") (pin "1") (pinfunction "1_1") (pintype "passive"))
      (node (ref "U5") (pin "4") (pinfunction "P0.24_4") (pintype "bidirectional"))
    )
    (net (code "15") (name "NRF_LED3") (class "Default")
      (node (ref "R29") (pin "1") (pinfunction "1_1") (pintype "passive"))
      (node (ref "U5") (pin "17") (pinfunction "P0.25_17") (pintype "bidirectional"))
    )
    (net (code "16") (name "NRF_LOCAL_RX") (class "Default")
      (node (ref "JP8") (pin "3") (pinfunction "3_3") (pintype "passive"))
      (node (ref "U5") (pin "27") (pinfunction "P0.11_27") (pintype "bidirectional"))
    )
    (net (code "17") (name "NRF_LOCAL_TX") (class "Default")
      (node (ref "JP8") (pin "4") (pinfunction "4_4") (pintype "passive"))
      (node (ref "U5") (pin "34") (pinfunction "P0.12_34") (pintype "bidirectional"))
    )
    (net (code "18") (name "NRF_RX") (class "Default")
      (node (ref "JP13") (pin "5") (pinfunction "5_5") (pintype "passive"))
      (node (ref "JP8") (pin "1") (pinfunction "1_1") (pintype "passive"))
    )
    (net (code "19") (name "NRF_SWCLK") (class "Default")
      (node (ref "JP11") (pin "5") (pinfunction "5_5") (pintype "passive"))
      (node (ref "U5") (pin "37") (pinfunction "SWCLK_37") (pintype "bidirectional"))
    )
    (net (code "20") (name "NRF_SWDIO") (class "Default")
      (node (ref "JP11") (pin "6") (pinfunction "6_6") (pintype "passive"))
      (node (ref "U5") (pin "24") (pinfunction "SWDIO/NRST_24") (pintype "bidirectional"))
    )
    (net (code "21") (name "NRF_SWO") (class "Default")
      (node (ref "JP12") (pin "6") (pinfunction "6_6") (pintype "passive"))
    )
    (net (code "22") (name "NRF_SWRST") (class "Default")
      (node (ref "JP12") (pin "5") (pinfunction "5_5") (pintype "passive"))
    )
    (net (code "23") (name "NRF_TX") (class "Default")
      (node (ref "JP13") (pin "6") (pinfunction "6_6") (pintype "passive"))
      (node (ref "JP8") (pin "2") (pinfunction "2_2") (pintype "passive"))
    )
    (net (code "24") (name "Net-(LED1-PadA)") (class "Default")
      (node (ref "LED1") (pin "A") (pinfunction "A_A") (pintype "passive"))
      (node (ref "R9") (pin "1") (pinfunction "1_1") (pintype "passive"))
    )
    (net (code "25") (name "Net-(LED2-PadC)") (class "Default")
      (node (ref "LED2") (pin "C") (pinfunction "C_C") (pintype "passive"))
      (node (ref "R8") (pin "2") (pinfunction "2_2") (pintype "passive"))
    )
    (net (code "26") (name "Net-(LED3-PadC)") (class "Default")
      (node (ref "LED3") (pin "C") (pinfunction "C_C") (pintype "passive"))
      (node (ref "R22") (pin "2") (pinfunction "2_2") (pintype "passive"))
    )
    (net (code "27") (name "Net-(LED4-PadC)") (class "Default")
      (node (ref "LED4") (pin "C") (pinfunction "C_C") (pintype "passive"))
      (node (ref "R23") (pin "2") (pinfunction "2_2") (pintype "passive"))
    )
    (net (code "28") (name "Net-(LED5-PadC)") (class "Default")
      (node (ref "LED5") (pin "C") (pinfunction "C_C") (pintype "passive"))
      (node (ref "R24") (pin "2") (pinfunction "2_2") (pintype "passive"))
    )
    (net (code "29") (name "Net-(LED6-PadC)") (class "Default")
      (node (ref "LED6") (pin "C") (pinfunction "C_C") (pintype "passive"))
      (node (ref "R25") (pin "2") (pinfunction "2_2") (pintype "passive"))
    )
    (net (code "30") (name "Net-(LED7-PadC)") (class "Default")
      (node (ref "LED7") (pin "C") (pinfunction "C_C") (pintype "passive"))
      (node (ref "R26") (pin "2") (pinfunction "2_2") (pintype "passive"))
    )
    (net (code "31") (name "Net-(LED8-PadC)") (class "Default")
      (node (ref "LED8") (pin "C") (pinfunction "C_C") (pintype "passive"))
      (node (ref "R27") (pin "2") (pinfunction "2_2") (pintype "passive"))
    )
    (net (code "32") (name "Net-(LED9-PadC)") (class "Default")
      (node (ref "LED9") (pin "C") (pinfunction "C_C") (pintype "passive"))
      (node (ref "R28") (pin "2") (pinfunction "2_2") (pintype "passive"))
    )
    (net (code "33") (name "Net-(LED10-PadC)") (class "Default")
      (node (ref "LED10") (pin "C") (pinfunction "C_C") (pintype "passive"))
      (node (ref "R29") (pin "2") (pinfunction "2_2") (pintype "passive"))
    )
    (net (code "34") (name "Net-(Q2-S)") (class "Default")
      (node (ref "Q2") (pin "2") (pinfunction "S_2") (pintype "bidirectional"))
      (node (ref "R5") (pin "1") (pinfunction "1_1") (pintype "passive"))
    )
    (net (code "35") (name "Net-(U1-BOOT0)") (class "Default")
      (node (ref "R1") (pin "1") (pinfunction "1_1") (pintype "passive"))
      (node (ref "U1") (pin "44") (pinfunction "BOOT0_44") (pintype "bidirectional"))
    )
    (net (code "36") (name "Net-(U1-PB12)") (class "Default")
      (node (ref "R7") (pin "1") (pinfunction "1_1") (pintype "passive"))
      (node (ref "U1") (pin "25") (pinfunction "PB12_25") (pintype "bidirectional"))
    )
    (net (code "37") (name "Net-(U1-PC13{slash}TAMPER{slash}RTC)") (class "Default")
      (node (ref "R2") (pin "2") (pinfunction "2_2") (pintype "passive"))
      (node (ref "U1") (pin "2") (pinfunction "PC13/TAMPER/RTC_2") (pintype "bidirectional"))
    )
    (net (code "38") (name "Net-(U2-BOOT0)") (class "Default")
      (node (ref "R11") (pin "2") (pinfunction "2_2") (pintype "passive"))
      (node (ref "U2") (pin "60") (pinfunction "BOOT0_60") (pintype "bidirectional"))
    )
    (net (code "39") (name "Net-(U3-VBUS_DET)") (class "Default")
      (node (ref "R12") (pin "2") (pinfunction "2_2") (pintype "passive"))
      (node (ref "U3") (pin "4") (pinfunction "VBUS_DET_4") (pintype "bidirectional"))
    )
    (net (code "40") (name "Net-(U4-VBUS_DET)") (class "Default")
      (node (ref "R13") (pin "2") (pinfunction "2_2") (pintype "passive"))
      (node (ref "U4") (pin "4") (pinfunction "VBUS_DET_4") (pintype "bidirectional"))
    )
    (net (code "41") (name "Net-(U7-ISET)") (class "Default")
      (node (ref "R20") (pin "2") (pinfunction "2_2") (pintype "passive"))
      (node (ref "U7") (pin "3") (pinfunction "ISET_3") (pintype "bidirectional"))
    )
    (net (code "42") (name "Net-(U8-ISET)") (class "Default")
      (node (ref "R33") (pin "2") (pinfunction "2_2") (pintype "passive"))
      (node (ref "U8") (pin "3") (pinfunction "ISET_3") (pintype "bidirectional"))
    )
    (net (code "43") (name "SPI_CS") (class "Default")
      (node (ref "R19") (pin "1") (pinfunction "1_1") (pintype "passive"))
      (node (ref "U2") (pin "17") (pinfunction "PA3_17") (pintype "bidirectional"))
      (node (ref "U5") (pin "30") (pinfunction "P0.05_30") (pintype "bidirectional"))
    )
    (net (code "44") (name "SPI_IRQ") (class "Default")
      (node (ref "R17") (pin "1") (pinfunction "1_1") (pintype "passive"))
      (node (ref "U2") (pin "20") (pinfunction "PA4_20") (pintype "bidirectional"))
      (node (ref "U5") (pin "31") (pinfunction "P0.06_31") (pintype "bidirectional"))
    )
    (net (code "45") (name "SPI_MISO") (class "Default")
      (node (ref "JP1") (pin "2") (pinfunction "2_2") (pintype "passive"))
      (node (ref "R30") (pin "2") (pinfunction "2_2") (pintype "passive"))
      (node (ref "U2") (pin "22") (pinfunction "PA6_22") (pintype "bidirectional"))
      (node (ref "U5") (pin "32") (pinfunction "P0.08_32") (pintype "bidirectional"))
    )
    (net (code "46") (name "SPI_MOSI") (class "Default")
      (node (ref "JP1") (pin "3") (pinfunction "3_3") (pintype "passive"))
      (node (ref "R21") (pin "2") (pinfunction "2_2") (pintype "passive"))
      (node (ref "U2") (pin "23") (pinfunction "PA7_23") (pintype "bidirectional"))
      (node (ref "U5") (pin "28") (pinfunction "P0.09_28") (pintype "bidirectional"))
    )
    (net (code "47") (name "SPI_SCK") (class "Default")
      (node (ref "JP1") (pin "1") (pinfunction "1_1") (pintype "passive"))
      (node (ref "R31") (pin "2") (pinfunction "2_2") (pintype "passive"))
      (node (ref "U2") (pin "21") (pinfunction "PA5_21") (pintype "bidirectional"))
      (node (ref "U5") (pin "29") (pinfunction "P0.07_29") (pintype "bidirectional"))
    )
    (net (code "48") (name "STLINK_LED") (class "Default")
      (node (ref "R8") (pin "1") (pinfunction "1_1") (pintype "passive"))
      (node (ref "R9") (pin "2") (pinfunction "2_2") (pintype "passive"))
      (node (ref "U1") (pin "30") (pinfunction "PA9_30") (pintype "bidirectional"))
    )
    (net (code "49") (name "STLINK_NRST") (class "Default")
      (node (ref "C3") (pin "2") (pinfunction "2_2") (pintype "passive"))
      (node (ref "R3") (pin "1") (pinfunction "1_1") (pintype "passive"))
      (node (ref "TP13") (pin "TP") (pinfunction "TP_TP") (pintype "input"))
      (node (ref "U1") (pin "7") (pinfunction "NRST_7") (pintype "bidirectional"))
    )
    (net (code "50") (name "STLINK_OSC_IN") (class "Default")
      (node (ref "C1") (pin "2") (pinfunction "2_2") (pintype "passive"))
      (node (ref "Q1") (pin "1") (pinfunction "1_1") (pintype "passive"))
      (node (ref "U1") (pin "5") (pinfunction "PD0/OSC_IN_5") (pintype "bidirectional"))
    )
    (net (code "51") (name "STLINK_OSC_OUT") (class "Default")
      (node (ref "C2") (pin "2") (pinfunction "2_2") (pintype "passive"))
      (node (ref "Q1") (pin "2") (pinfunction "2_2") (pintype "passive"))
      (node (ref "U1") (pin "6") (pinfunction "PD1/OSC_OUT_6") (pintype "bidirectional"))
    )
    (net (code "52") (name "STLINK_RX") (class "Default")
      (node (ref "JP13") (pin "4") (pinfunction "4_4") (pintype "passive"))
      (node (ref "U1") (pin "13") (pinfunction "PA3_13") (pintype "bidirectional"))
    )
    (net (code "53") (name "STLINK_SWCLK") (class "Default")
      (node (ref "TP1") (pin "TP") (pinfunction "TP_TP") (pintype "input"))
      (node (ref "U1") (pin "37") (pinfunction "PA14/SWCLK_37") (pintype "bidirectional"))
    )
    (net (code "54") (name "STLINK_SWDIO") (class "Default")
      (node (ref "TP2") (pin "TP") (pinfunction "TP_TP") (pintype "input"))
      (node (ref "U1") (pin "34") (pinfunction "PA13/SWDIO_34") (pintype "bidirectional"))
    )
    (net (code "55") (name "STLINK_TX") (class "Default")
      (node (ref "JP13") (pin "3") (pinfunction "3_3") (pintype "passive"))
      (node (ref "U1") (pin "12") (pinfunction "PA2_12") (pintype "bidirectional"))
    )
    (net (code "56") (name "STLINK_USB_ID") (class "Default")
      (node (ref "CN1") (pin "ID") (pinfunction "ID_ID") (pintype "passive"))
      (node (ref "R4") (pin "1") (pinfunction "1_1") (pintype "passive"))
    )
    (net (code "57") (name "STLINK_USB_N") (class "Default")
      (node (ref "CN1") (pin "DM") (pinfunction "DM_DM") (pintype "passive"))
      (node (ref "U1") (pin "32") (pinfunction "PA11/USBDM_32") (pintype "bidirectional"))
    )
    (net (code "58") (name "STLINK_USB_P") (class "Default")
      (node (ref "CN1") (pin "DP") (pinfunction "DP_DP") (pintype "passive"))
      (node (ref "R5") (pin "2") (pinfunction "2_2") (pintype "passive"))
      (node (ref "U1") (pin "33") (pinfunction "PA12/USBDP_33") (pintype "bidirectional"))
    )
    (net (code "59") (name "STLINK_USB_RENUMN") (class "Default")
      (node (ref "Q2") (pin "1") (pinfunction "G_1") (pintype "bidirectional"))
      (node (ref "R6") (pin "1") (pinfunction "1_1") (pintype "passive"))
      (node (ref "U1") (pin "38") (pinfunction "PA15_38") (pintype "bidirectional"))
    )
    (net (code "60") (name "STLINK_USB_VBUS") (class "Default")
      (node (ref "CN1") (pin "VBUS") (pinfunction "VBUS_VBUS") (pintype "passive"))
      (node (ref "D1") (pin "A") (pinfunction "A_A") (pintype "passive"))
      (node (ref "Q4") (pin "1") (pinfunction "G_1") (pintype "bidirectional"))
      (node (ref "R16") (pin "2") (pinfunction "2_2") (pintype "passive"))
    )
    (net (code "61") (name "STM_DBG_PIN0") (class "Default")
      (node (ref "JP9") (pin "1") (pinfunction "1_1") (pintype "passive"))
      (node (ref "U2") (pin "26") (pinfunction "PB0_26") (pintype "bidirectional"))
    )
    (net (code "62") (name "STM_DBG_PIN1") (class "Default")
      (node (ref "JP9") (pin "2") (pinfunction "2_2") (pintype "passive"))
      (node (ref "U2") (pin "27") (pinfunction "PB1_27") (pintype "bidirectional"))
    )
    (net (code "63") (name "STM_DBG_PIN2") (class "Default")
      (node (ref "JP9") (pin "3") (pinfunction "3_3") (pintype "passive"))
      (node (ref "U2") (pin "28") (pinfunction "PB2_28") (pintype "bidirectional"))
    )
    (net (code "64") (name "STM_DBG_PIN3") (class "Default")
      (node (ref "JP9") (pin "4") (pinfunction "4_4") (pintype "passive"))
      (node (ref "U2") (pin "29") (pinfunction "PB10_29") (pintype "bidirectional"))
    )
    (net (code "65") (name "STM_DBG_TP_0") (class "Default")
      (node (ref "TP4") (pin "TP") (pinfunction "TP_TP") (pintype "input"))
      (node (ref "U2") (pin "56") (pinfunction "PB4_56") (pintype "bidirectional"))
    )
    (net (code "66") (name "STM_DBG_TP_1") (class "Default")
      (node (ref "TP5") (pin "TP") (pinfunction "TP_TP") (pintype "input"))
      (node (ref "U2") (pin "57") (pinfunction "PB5_57") (pintype "bidirectional"))
    )
    (net (code "67") (name "STM_DBG_TP_2") (class "Default")
      (node (ref "TP6") (pin "TP") (pinfunction "TP_TP") (pintype "input"))
      (node (ref "U2") (pin "61") (pinfunction "PB8_61") (pintype "bidirectional"))
    )
    (net (code "68") (name "STM_DBG_TP_3") (class "Default")
      (node (ref "TP7") (pin "TP") (pinfunction "TP_TP") (pintype "input"))
      (node (ref "U2") (pin "62") (pinfunction "PB9_62") (pintype "bidirectional"))
    )
    (net (code "69") (name "STM_LED0") (class "Default")
      (node (ref "R22") (pin "1") (pinfunction "1_1") (pintype "passive"))
      (node (ref "U2") (pin "37") (pinfunction "PC6_37") (pintype "bidirectional"))
    )
    (net (code "70") (name "STM_LED1") (class "Default")
      (node (ref "R23") (pin "1") (pinfunction "1_1") (pintype "passive"))
      (node (ref "U2") (pin "38") (pinfunction "PC7_38") (pintype "bidirectional"))
    )
    (net (code "71") (name "STM_LED2") (class "Default")
      (node (ref "R24") (pin "1") (pinfunction "1_1") (pintype "passive"))
      (node (ref "U2") (pin "39") (pinfunction "PC8_39") (pintype "bidirectional"))
    )
    (net (code "72") (name "STM_LED3") (class "Default")
      (node (ref "R25") (pin "1") (pinfunction "1_1") (pintype "passive"))
      (node (ref "U2") (pin "40") (pinfunction "PC9_40") (pintype "bidirectional"))
    )
    (net (code "73") (name "STM_OSC_IN") (class "Default")
      (node (ref "C8") (pin "2") (pinfunction "2_2") (pintype "passive"))
      (node (ref "Q3") (pin "1") (pinfunction "1_1") (pintype "passive"))
      (node (ref "U2") (pin "5") (pinfunction "PH0/OSC_IN_5") (pintype "bidirectional"))
    )
    (net (code "74") (name "STM_OSC_OUT") (class "Default")
      (node (ref "C9") (pin "2") (pinfunction "2_2") (pintype "passive"))
      (node (ref "Q3") (pin "2") (pinfunction "2_2") (pintype "passive"))
      (node (ref "U2") (pin "6") (pinfunction "PH1/OSC_OUT_6") (pintype "bidirectional"))
    )
    (net (code "75") (name "STM_RX") (class "Default")
      (node (ref "JP13") (pin "1") (pinfunction "1_1") (pintype "passive"))
      (node (ref "U2") (pin "59") (pinfunction "PB7_59") (pintype "bidirectional"))
    )
    (net (code "76") (name "STM_SWCLK") (class "Default")
      (node (ref "JP11") (pin "1") (pinfunction "1_1") (pintype "passive"))
      (node (ref "U2") (pin "49") (pinfunction "PA14_49") (pintype "bidirectional"))
    )
    (net (code "77") (name "STM_SWDIO") (class "Default")
      (node (ref "JP11") (pin "2") (pinfunction "2_2") (pintype "passive"))
      (node (ref "U2") (pin "46") (pinfunction "PA13_46") (pintype "bidirectional"))
    )
    (net (code "78") (name "STM_SWO") (class "Default")
      (node (ref "JP12") (pin "2") (pinfunction "2_2") (pintype "passive"))
      (node (ref "U2") (pin "55") (pinfunction "PB3_55") (pintype "bidirectional"))
    )
    (net (code "79") (name "STM_SWRST") (class "Default")
      (node (ref "C10") (pin "2") (pinfunction "2_2") (pintype "passive"))
      (node (ref "JP12") (pin "1") (pinfunction "1_1") (pintype "passive"))
      (node (ref "R10") (pin "1") (pinfunction "1_1") (pintype "passive"))
      (node (ref "TP3") (pin "TP") (pinfunction "TP_TP") (pintype "input"))
      (node (ref "U2") (pin "7") (pinfunction "NRST_7") (pintype "bidirectional"))
    )
    (net (code "80") (name "STM_TX") (class "Default")
      (node (ref "JP13") (pin "2") (pinfunction "2_2") (pintype "passive"))
      (node (ref "U2") (pin "58") (pinfunction "PB6_58") (pintype "bidirectional"))
    )
    (net (code "81") (name "SWCLK") (class "Default")
      (node (ref "JP11") (pin "3") (pinfunction "3_3") (pintype "passive"))
      (node (ref "U1") (pin "15") (pinfunction "PA5_15") (pintype "bidirectional"))
      (node (ref "U1") (pin "26") (pinfunction "PB13_26") (pintype "bidirectional"))
    )
    (net (code "82") (name "SWDIO") (class "Default")
      (node (ref "JP11") (pin "4") (pinfunction "4_4") (pintype "passive"))
      (node (ref "R7") (pin "2") (pinfunction "2_2") (pintype "passive"))
      (node (ref "U1") (pin "27") (pinfunction "PB14_27") (pintype "bidirectional"))
    )
    (net (code "83") (name "SWO") (class "Default")
      (node (ref "JP12") (pin "4") (pinfunction "4_4") (pintype "passive"))
      (node (ref "U1") (pin "31") (pinfunction "PA10_31") (pintype "bidirectional"))
    )
    (net (code "84") (name "SWRST") (class "Default")
      (node (ref "JP12") (pin "3") (pinfunction "3_3") (pintype "passive"))
      (node (ref "U1") (pin "18") (pinfunction "PB0_18") (pintype "bidirectional"))
    )
    (net (code "85") (name "UART_NRF2STM") (class "Default")
      (node (ref "JP8") (pin "6") (pinfunction "6_6") (pintype "passive"))
      (node (ref "U2") (pin "52") (pinfunction "PC11_52") (pintype "bidirectional"))
    )
    (net (code "86") (name "UART_STM2NRF") (class "Default")
      (node (ref "JP8") (pin "5") (pinfunction "5_5") (pintype "passive"))
      (node (ref "U2") (pin "51") (pinfunction "PC10_51") (pintype "bidirectional"))
    )
    (net (code "87") (name "USB_FS_CC1") (class "Default")
      (node (ref "CN2") (pin "A5") (pinfunction "CC1_A5") (pintype "bidirectional"))
      (node (ref "U3") (pin "1") (pinfunction "CC1_1") (pintype "bidirectional"))
    )
    (net (code "88") (name "USB_FS_CC2") (class "Default")
      (node (ref "CN2") (pin "B5") (pinfunction "CC2_B5") (pintype "bidirectional"))
      (node (ref "U3") (pin "2") (pinfunction "CC2_2") (pintype "bidirectional"))
    )
    (net (code "89") (name "USB_FS_HS_VBUS") (class "Default")
      (node (ref "JP7") (pin "2") (pinfunction "2_2") (pintype "passive"))
      (node (ref "Q4") (pin "2") (pinfunction "S_2") (pintype "bidirectional"))
    )
    (net (code "90") (name "USB_FS_ID") (class "Default")
      (node (ref "R14") (pin "2") (pinfunction "2_2") (pintype "passive"))
      (node (ref "U2") (pin "43") (pinfunction "PA10_43") (pintype "bidirectional"))
      (node (ref "U3") (pin "9") (pinfunction "ID_9") (pintype "bidirectional"))
    )
    (net (code "91") (name "USB_FS_N") (class "Default")
      (node (ref "CN2") (pin "A7") (pinfunction "DM_1_A7") (pintype "bidirectional"))
      (node (ref "CN2") (pin "B7") (pinfunction "DM_2_B7") (pintype "bidirectional"))
      (node (ref "U2") (pin "44") (pinfunction "PA11_44") (pintype "bidirectional"))
    )
    (net (code "92") (name "USB_FS_ON") (class "Default")
      (node (ref "R18") (pin "2") (pinfunction "2_2") (pintype "passive"))
      (node (ref "U2") (pin "41") (pinfunction "PA8_41") (pintype "bidirectional"))
      (node (ref "U7") (pin "4") (pinfunction "EN_4") (pintype "bidirectional"))
    )
    (net (code "93") (name "USB_FS_P") (class "Default")
      (node (ref "CN2") (pin "A6") (pinfunction "DP_1_A6") (pintype "bidirectional"))
      (node (ref "CN2") (pin "B6") (pinfunction "DP_2_B6") (pintype "bidirectional"))
      (node (ref "U2") (pin "45") (pinfunction "PA12_45") (pintype "bidirectional"))
    )
    (net (code "94") (name "USB_FS_VBUS") (class "Default")
      (node (ref "C22") (pin "1") (pinfunction "1_1") (pintype "passive"))
      (node (ref "CN2") (pin "A4") (pinfunction "VBUS_A4") (pintype "bidirectional"))
      (node (ref "CN2") (pin "A9") (pinfunction "VBUS_A9") (pintype "bidirectional"))
      (node (ref "JP7") (pin "3") (pinfunction "3_3") (pintype "passive"))
      (node (ref "R12") (pin "1") (pinfunction "1_1") (pintype "passive"))
      (node (ref "U2") (pin "42") (pinfunction "PA9_42") (pintype "bidirectional"))
      (node (ref "U7") (pin "1") (pinfunction "OUT_1") (pintype "bidirectional"))
    )
    (net (code "95") (name "USB_HS_CC1") (class "Default")
      (node (ref "CN3") (pin "A5") (pinfunction "CC1_A5") (pintype "bidirectional"))
      (node (ref "U4") (pin "1") (pinfunction "CC1_1") (pintype "bidirectional"))
    )
    (net (code "96") (name "USB_HS_CC2") (class "Default")
      (node (ref "CN3") (pin "B5") (pinfunction "CC2_B5") (pintype "bidirectional"))
      (node (ref "U4") (pin "2") (pinfunction "CC2_2") (pintype "bidirectional"))
    )
    (net (code "97") (name "USB_HS_ID") (class "Default")
      (node (ref "R15") (pin "2") (pinfunction "2_2") (pintype "passive"))
      (node (ref "U2") (pin "33") (pinfunction "PB12_33") (pintype "bidirectional"))
      (node (ref "U4") (pin "9") (pinfunction "ID_9") (pintype "bidirectional"))
    )
    (net (code "98") (name "USB_HS_N") (class "Default")
      (node (ref "CN3") (pin "A7") (pinfunction "DM_1_A7") (pintype "bidirectional"))
      (node (ref "CN3") (pin "B7") (pinfunction "DM_2_B7") (pintype "bidirectional"))
      (node (ref "U2") (pin "35") (pinfunction "PB14_35") (pintype "bidirectional"))
    )
    (net (code "99") (name "USB_HS_ON") (class "Default")
      (node (ref "R32") (pin "2") (pinfunction "2_2") (pintype "passive"))
      (node (ref "U2") (pin "30") (pinfunction "PB11_30") (pintype "bidirectional"))
      (node (ref "U8") (pin "4") (pinfunction "EN_4") (pintype "bidirectional"))
    )
    (net (code "100") (name "USB_HS_P") (class "Default")
      (node (ref "CN3") (pin "A6") (pinfunction "DP_1_A6") (pintype "bidirectional"))
      (node (ref "CN3") (pin "B6") (pinfunction "DP_2_B6") (pintype "bidirectional"))
      (node (ref "U2") (pin "36") (pinfunction "PB15_36") (pintype "bidirectional"))
    )
    (net (code "101") (name "USB_HS_VBUS") (class "Default")
      (node (ref "C23") (pin "1") (pinfunction "1_1") (pintype "passive"))
      (node (ref "CN3") (pin "A4") (pinfunction "VBUS_A4") (pintype "bidirectional"))
      (node (ref "CN3") (pin "A9") (pinfunction "VBUS_A9") (pintype "bidirectional"))
      (node (ref "JP7") (pin "1") (pinfunction "1_1") (pintype "passive"))
      (node (ref "R13") (pin "1") (pinfunction "1_1") (pintype "passive"))
      (node (ref "U2") (pin "34") (pinfunction "PB13_34") (pintype "bidirectional"))
      (node (ref "U8") (pin "1") (pinfunction "OUT_1") (pintype "bidirectional"))
    )
    (net (code "102") (name "unconnected-(CN2-SBU1-PadA8)") (class "Default")
      (node (ref "CN2") (pin "A8") (pinfunction "SBU1_A8") (pintype "bidirectional"))
    )
    (net (code "103") (name "unconnected-(CN2-SBU2-PadB8)") (class "Default")
      (node (ref "CN2") (pin "B8") (pinfunction "SBU2_B8") (pintype "bidirectional"))
    )
    (net (code "104") (name "unconnected-(CN3-SBU1-PadA8)") (class "Default")
      (node (ref "CN3") (pin "A8") (pinfunction "SBU1_A8") (pintype "bidirectional"))
    )
    (net (code "105") (name "unconnected-(CN3-SBU2-PadB8)") (class "Default")
      (node (ref "CN3") (pin "B8") (pinfunction "SBU2_B8") (pintype "bidirectional"))
    )
    (net (code "106") (name "unconnected-(U1-PA0{slash}WKUP-Pad10)") (class "Default")
      (node (ref "U1") (pin "10") (pinfunction "PA0/WKUP_10") (pintype "bidirectional"))
    )
    (net (code "107") (name "unconnected-(U1-PA1-Pad11)") (class "Default")
      (node (ref "U1") (pin "11") (pinfunction "PA1_11") (pintype "bidirectional"))
    )
    (net (code "108") (name "unconnected-(U1-PA4-Pad14)") (class "Default")
      (node (ref "U1") (pin "14") (pinfunction "PA4_14") (pintype "bidirectional"))
    )
    (net (code "109") (name "unconnected-(U1-PA6-Pad16)") (class "Default")
      (node (ref "U1") (pin "16") (pinfunction "PA6_16") (pintype "bidirectional"))
    )
    (net (code "110") (name "unconnected-(U1-PA7-Pad17)") (class "Default")
      (node (ref "U1") (pin "17") (pinfunction "PA7_17") (pintype "bidirectional"))
    )
    (net (code "111") (name "unconnected-(U1-PA8-Pad29)") (class "Default")
      (node (ref "U1") (pin "29") (pinfunction "PA8_29") (pintype "bidirectional"))
    )
    (net (code "112") (name "unconnected-(U1-PB1-Pad19)") (class "Default")
      (node (ref "U1") (pin "19") (pinfunction "PB1_19") (pintype "bidirectional"))
    )
    (net (code "113") (name "unconnected-(U1-PB2{slash}BOOT1-Pad20)") (class "Default")
      (node (ref "U1") (pin "20") (pinfunction "PB2/BOOT1_20") (pintype "bidirectional"))
    )
    (net (code "114") (name "unconnected-(U1-PB4-Pad40)") (class "Default")
      (node (ref "U1") (pin "40") (pinfunction "PB4_40") (pintype "bidirectional"))
    )
    (net (code "115") (name "unconnected-(U1-PB5-Pad41)") (class "Default")
      (node (ref "U1") (pin "41") (pinfunction "PB5_41") (pintype "bidirectional"))
    )
    (net (code "116") (name "unconnected-(U1-PB6-Pad42)") (class "Default")
      (node (ref "U1") (pin "42") (pinfunction "PB6_42") (pintype "bidirectional"))
    )
    (net (code "117") (name "unconnected-(U1-PB7-Pad43)") (class "Default")
      (node (ref "U1") (pin "43") (pinfunction "PB7_43") (pintype "bidirectional"))
    )
    (net (code "118") (name "unconnected-(U1-PB8-Pad45)") (class "Default")
      (node (ref "U1") (pin "45") (pinfunction "PB8_45") (pintype "bidirectional"))
    )
    (net (code "119") (name "unconnected-(U1-PB9-Pad46)") (class "Default")
      (node (ref "U1") (pin "46") (pinfunction "PB9_46") (pintype "bidirectional"))
    )
    (net (code "120") (name "unconnected-(U1-PB10-Pad21)") (class "Default")
      (node (ref "U1") (pin "21") (pinfunction "PB10_21") (pintype "bidirectional"))
    )
    (net (code "121") (name "unconnected-(U1-PB11-Pad22)") (class "Default")
      (node (ref "U1") (pin "22") (pinfunction "PB11_22") (pintype "bidirectional"))
    )
    (net (code "122") (name "unconnected-(U1-PB15-Pad28)") (class "Default")
      (node (ref "U1") (pin "28") (pinfunction "PB15_28") (pintype "bidirectional"))
    )
    (net (code "123") (name "unconnected-(U1-PC14{slash}OSC32_IN-Pad3)") (class "Default")
      (node (ref "U1") (pin "3") (pinfunction "PC14/OSC32_IN_3") (pintype "bidirectional"))
    )
    (net (code "124") (name "unconnected-(U1-PC15{slash}OSC32_OUT-Pad4)") (class "Default")
      (node (ref "U1") (pin "4") (pinfunction "PC15/OSC32_OUT_4") (pintype "bidirectional"))
    )
    (net (code "125") (name "unconnected-(U2-PA0-Pad14)") (class "Default")
      (node (ref "U2") (pin "14") (pinfunction "PA0_14") (pintype "bidirectional"))
    )
    (net (code "126") (name "unconnected-(U2-PA1-Pad15)") (class "Default")
      (node (ref "U2") (pin "15") (pinfunction "PA1_15") (pintype "bidirectional"))
    )
    (net (code "127") (name "unconnected-(U2-PA2-Pad16)") (class "Default")
      (node (ref "U2") (pin "16") (pinfunction "PA2_16") (pintype "bidirectional"))
    )
    (net (code "128") (name "unconnected-(U2-PA15-Pad50)") (class "Default")
      (node (ref "U2") (pin "50") (pinfunction "PA15_50") (pintype "bidirectional"))
    )
    (net (code "129") (name "unconnected-(U2-PC0-Pad8)") (class "Default")
      (node (ref "U2") (pin "8") (pinfunction "PC0_8") (pintype "bidirectional"))
    )
    (net (code "130") (name "unconnected-(U2-PC1-Pad9)") (class "Default")
      (node (ref "U2") (pin "9") (pinfunction "PC1_9") (pintype "bidirectional"))
    )
    (net (code "131") (name "unconnected-(U2-PC2-Pad10)") (class "Default")
      (node (ref "U2") (pin "10") (pinfunction "PC2_10") (pintype "bidirectional"))
    )
    (net (code "132") (name "unconnected-(U2-PC3-Pad11)") (class "Default")
      (node (ref "U2") (pin "11") (pinfunction "PC3_11") (pintype "bidirectional"))
    )
    (net (code "133") (name "unconnected-(U2-PC4-Pad24)") (class "Default")
      (node (ref "U2") (pin "24") (pinfunction "PC4_24") (pintype "bidirectional"))
    )
    (net (code "134") (name "unconnected-(U2-PC5-Pad25)") (class "Default")
      (node (ref "U2") (pin "25") (pinfunction "PC5_25") (pintype "bidirectional"))
    )
    (net (code "135") (name "unconnected-(U2-PC12-Pad53)") (class "Default")
      (node (ref "U2") (pin "53") (pinfunction "PC12_53") (pintype "bidirectional"))
    )
    (net (code "136") (name "unconnected-(U2-PC13-Pad2)") (class "Default")
      (node (ref "U2") (pin "2") (pinfunction "PC13_2") (pintype "bidirectional"))
    )
    (net (code "137") (name "unconnected-(U2-PC14{slash}OSC32_IN-Pad3)") (class "Default")
      (node (ref "U2") (pin "3") (pinfunction "PC14/OSC32_IN_3") (pintype "bidirectional"))
    )
    (net (code "138") (name "unconnected-(U2-PC15{slash}OSC32_OUT-Pad4)") (class "Default")
      (node (ref "U2") (pin "4") (pinfunction "PC15/OSC32_OUT_4") (pintype "bidirectional"))
    )
    (net (code "139") (name "unconnected-(U2-PD2-Pad54)") (class "Default")
      (node (ref "U2") (pin "54") (pinfunction "PD2_54") (pintype "bidirectional"))
    )
    (net (code "140") (name "unconnected-(U2-VCAP1-Pad31)") (class "Default")
      (node (ref "U2") (pin "31") (pinfunction "VCAP1_31") (pintype "bidirectional"))
    )
    (net (code "141") (name "unconnected-(U2-VCAP2-Pad47)") (class "Default")
      (node (ref "U2") (pin "47") (pinfunction "VCAP2_47") (pintype "bidirectional"))
    )
    (net (code "142") (name "unconnected-(U3-ADDR-Pad5)") (class "Default")
      (node (ref "U3") (pin "5") (pinfunction "ADDR_5") (pintype "bidirectional"))
    )
    (net (code "143") (name "unconnected-(U3-INT_N{slash}OUT3-Pad6)") (class "Default")
      (node (ref "U3") (pin "6") (pinfunction "INT_N/OUT3_6") (pintype "bidirectional"))
    )
    (net (code "144") (name "unconnected-(U3-PORT-Pad3)") (class "Default")
      (node (ref "U3") (pin "3") (pinfunction "PORT_3") (pintype "bidirectional"))
    )
    (net (code "145") (name "unconnected-(U3-SCL{slash}OUT2-Pad8)") (class "Default")
      (node (ref "U3") (pin "8") (pinfunction "SCL/OUT2_8") (pintype "bidirectional"))
    )
    (net (code "146") (name "unconnected-(U3-SDA{slash}OUT1-Pad7)") (class "Default")
      (node (ref "U3") (pin "7") (pinfunction "SDA/OUT1_7") (pintype "bidirectional"))
    )
    (net (code "147") (name "unconnected-(U4-ADDR-Pad5)") (class "Default")
      (node (ref "U4") (pin "5") (pinfunction "ADDR_5") (pintype "bidirectional"))
    )
    (net (code "148") (name "unconnected-(U4-INT_N{slash}OUT3-Pad6)") (class "Default")
      (node (ref "U4") (pin "6") (pinfunction "INT_N/OUT3_6") (pintype "bidirectional"))
    )
    (net (code "149") (name "unconnected-(U4-PORT-Pad3)") (class "Default")
      (node (ref "U4") (pin "3") (pinfunction "PORT_3") (pintype "bidirectional"))
    )
    (net (code "150") (name "unconnected-(U4-SCL{slash}OUT2-Pad8)") (class "Default")
      (node (ref "U4") (pin "8") (pinfunction "SCL/OUT2_8") (pintype "bidirectional"))
    )
    (net (code "151") (name "unconnected-(U4-SDA{slash}OUT1-Pad7)") (class "Default")
      (node (ref "U4") (pin "7") (pinfunction "SDA/OUT1_7") (pintype "bidirectional"))
    )
    (net (code "152") (name "unconnected-(U5-P0.00-Pad13)") (class "Default")
      (node (ref "U5") (pin "13") (pinfunction "P0.00_13") (pintype "bidirectional"))
    )
    (net (code "153") (name "unconnected-(U5-P0.10-Pad33)") (class "Default")
      (node (ref "U5") (pin "33") (pinfunction "P0.10_33") (pintype "bidirectional"))
    )
    (net (code "154") (name "unconnected-(U5-P0.17-Pad23)") (class "Default")
      (node (ref "U5") (pin "23") (pinfunction "P0.17_23") (pintype "bidirectional"))
    )
    (net (code "155") (name "unconnected-(U5-P0.18-Pad22)") (class "Default")
      (node (ref "U5") (pin "22") (pinfunction "P0.18_22") (pintype "bidirectional"))
    )
    (net (code "156") (name "unconnected-(U5-P0.19-Pad38)") (class "Default")
      (node (ref "U5") (pin "38") (pinfunction "P0.19_38") (pintype "bidirectional"))
    )
    (net (code "157") (name "unconnected-(U5-P0.20-Pad39)") (class "Default")
      (node (ref "U5") (pin "39") (pinfunction "P0.20_39") (pintype "bidirectional"))
    )
    (net (code "158") (name "unconnected-(U5-P0.21-Pad19)") (class "Default")
      (node (ref "U5") (pin "19") (pinfunction "P0.21_19") (pintype "bidirectional"))
    )
    (net (code "159") (name "unconnected-(U5-P0.28-Pad6)") (class "Default")
      (node (ref "U5") (pin "6") (pinfunction "P0.28_6") (pintype "bidirectional"))
    )
    (net (code "160") (name "unconnected-(U5-P0.29-Pad15)") (class "Default")
      (node (ref "U5") (pin "15") (pinfunction "P0.29_15") (pintype "bidirectional"))
    )
    (net (code "161") (name "unconnected-(U5-P0.30-Pad8)") (class "Default")
      (node (ref "U5") (pin "8") (pinfunction "P0.30_8") (pintype "bidirectional"))
    )
  )
)
